# timer.net
KiCad netlist of a schematic drawn in Altium Designer
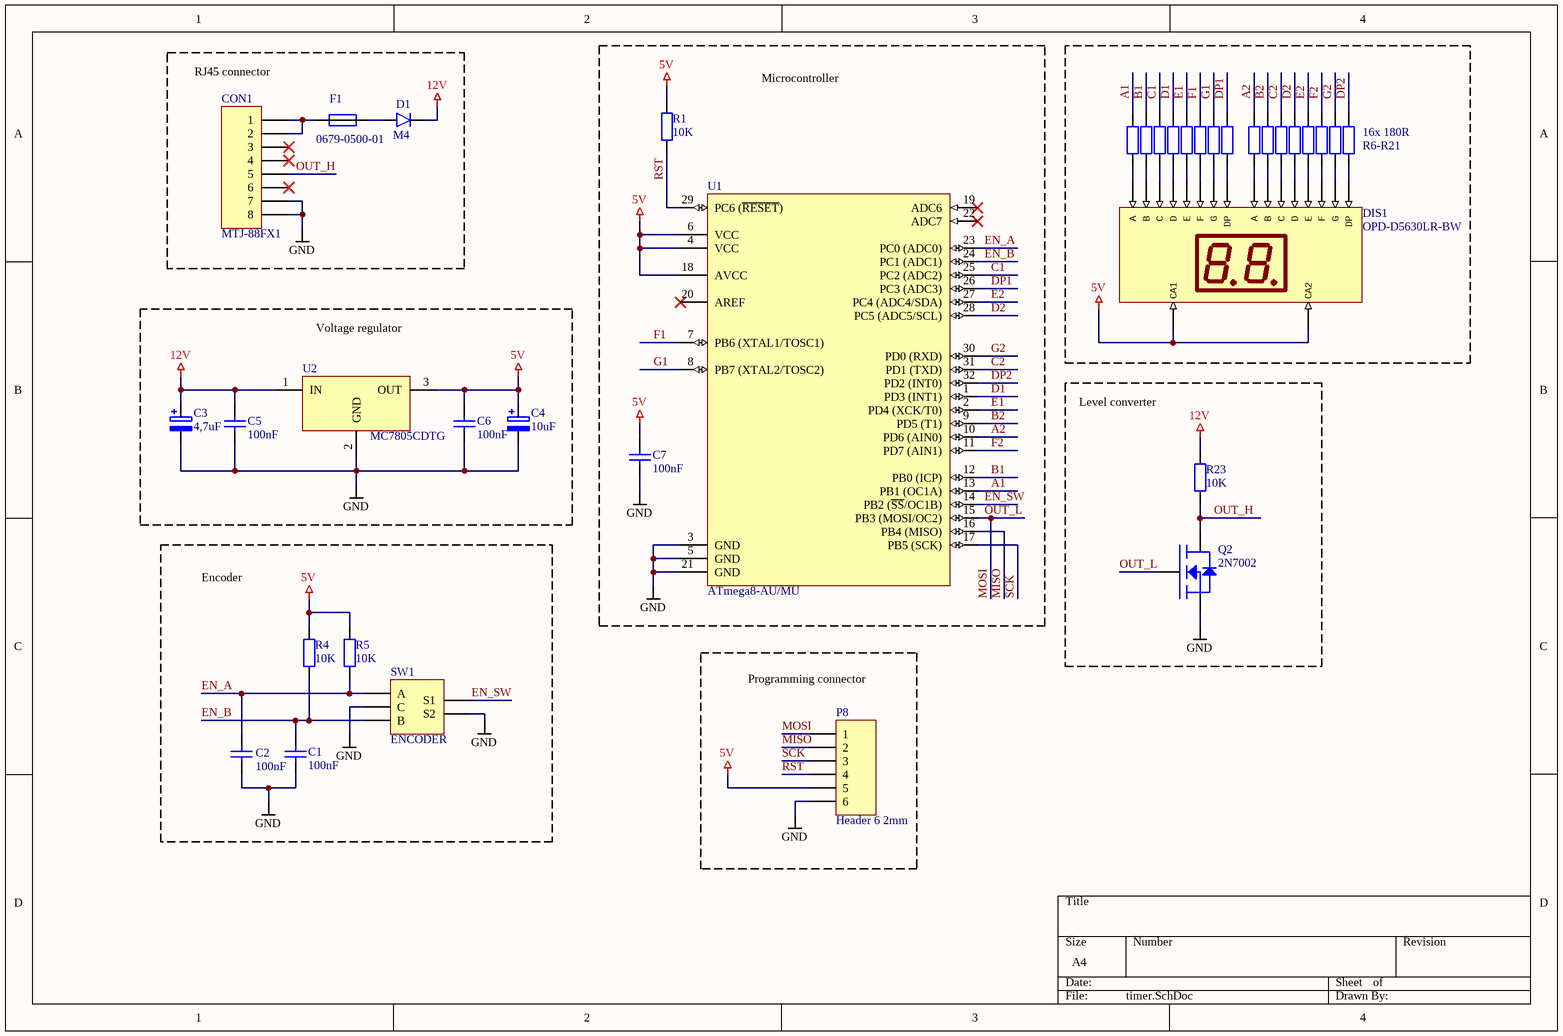
[diagram p0: timer.SchDoc]

(export (version "E")
  (design (tool "Eeschema 10.0.6"))
  (components
    (comp (ref "C1")
      (value "100nF")
      (footprint "C0805")
      (description "Capacitor")
      (libsource (lib "Library") (part "Cap"))
    )
    (comp (ref "C2")
      (value "100nF")
      (footprint "C0805")
      (description "Capacitor")
      (libsource (lib "Library") (part "Cap"))
    )
    (comp (ref "C3")
      (value "4,7uF")
      (footprint "TANC_B")
      (description "Capacitor Polarized")
      (libsource (lib "Library") (part "Cap_Pol"))
    )
    (comp (ref "C4")
      (value "10uF")
      (footprint "TANC_B")
      (description "Capacitor Polarized")
      (libsource (lib "Library") (part "Cap_Pol"))
    )
    (comp (ref "C5")
      (value "100nF")
      (footprint "C0805")
      (description "Capacitor")
      (libsource (lib "Library") (part "Cap"))
    )
    (comp (ref "C6")
      (value "100nF")
      (footprint "C0805")
      (description "Capacitor")
      (libsource (lib "Library") (part "Cap"))
    )
    (comp (ref "C7")
      (value "100nF")
      (footprint "C0805")
      (description "Capacitor")
      (libsource (lib "Library") (part "Cap"))
    )
    (comp (ref "CON1")
      (value "MTJ-88FX1")
      (footprint "MTJ-88FX1")
      (libsource (lib "Connectors") (part "MTJ-88FX1"))
    )
    (comp (ref "D1") (value "M4") (footprint "SMA") (libsource (lib "Library") (part "Diode")))
    (comp (ref "DIS1")
      (value "OPD-D5630LR-BW")
      (footprint "OPD-D5631LR-BW")
      (libsource (lib "Library") (part "2x8SEGMENTS"))
    )
    (comp (ref "F1")
      (value "0679-0500-01")
      (footprint "0679-0500-01")
      (description "Bezpiecznik: topikowy; szybki; ceramiczny; 500mA; 125VAC; 125VDC")
      (libsource (lib "Library") (part "0679-0500-01"))
    )
    (comp (ref "P8")
      (value "Header 6 2mm")
      (footprint "MA06-1_2mm")
      (description "Header, 6-Pin")
      (libsource (lib "Connectors") (part "Header 6"))
    )
    (comp (ref "Q2")
      (value "2N7002")
      (footprint "SOT23")
      (description "N-MOSFET")
      (libsource (lib "Library") (part "2N7002(GSD)"))
    )
    (comp (ref "R1")
      (value "10K")
      (footprint "R0805")
      (description "Resistor")
      (libsource (lib "") (part "Res_1"))
    )
    (comp (ref "R4")
      (value "10K")
      (footprint "R0805")
      (description "Resistor")
      (libsource (lib "Library") (part "Res"))
    )
    (comp (ref "R5")
      (value "10K")
      (footprint "R0805")
      (description "Resistor")
      (libsource (lib "Library") (part "Res"))
    )
    (comp (ref "R6")
      (value "180R")
      (footprint "R0805")
      (description "Resistor")
      (libsource (lib "Library") (part "Res"))
    )
    (comp (ref "R7")
      (value "180R")
      (footprint "R0805")
      (description "Resistor")
      (libsource (lib "Library") (part "Res"))
    )
    (comp (ref "R8")
      (value "180R")
      (footprint "R0805")
      (description "Resistor")
      (libsource (lib "Library") (part "Res"))
    )
    (comp (ref "R9")
      (value "180R")
      (footprint "R0805")
      (description "Resistor")
      (libsource (lib "Library") (part "Res"))
    )
    (comp (ref "R10")
      (value "180R")
      (footprint "R0805")
      (description "Resistor")
      (libsource (lib "Library") (part "Res"))
    )
    (comp (ref "R11")
      (value "180R")
      (footprint "R0805")
      (description "Resistor")
      (libsource (lib "Library") (part "Res"))
    )
    (comp (ref "R12")
      (value "180R")
      (footprint "R0805")
      (description "Resistor")
      (libsource (lib "Library") (part "Res"))
    )
    (comp (ref "R13")
      (value "180R")
      (footprint "R0805")
      (description "Resistor")
      (libsource (lib "Library") (part "Res"))
    )
    (comp (ref "R14")
      (value "180R")
      (footprint "R0805")
      (description "Resistor")
      (libsource (lib "Library") (part "Res"))
    )
    (comp (ref "R15")
      (value "180R")
      (footprint "R0805")
      (description "Resistor")
      (libsource (lib "Library") (part "Res"))
    )
    (comp (ref "R16")
      (value "180R")
      (footprint "R0805")
      (description "Resistor")
      (libsource (lib "Library") (part "Res"))
    )
    (comp (ref "R17")
      (value "180R")
      (footprint "R0805")
      (description "Resistor")
      (libsource (lib "Library") (part "Res"))
    )
    (comp (ref "R18")
      (value "180R")
      (footprint "R0805")
      (description "Resistor")
      (libsource (lib "Library") (part "Res"))
    )
    (comp (ref "R19")
      (value "180R")
      (footprint "R0805")
      (description "Resistor")
      (libsource (lib "Library") (part "Res"))
    )
    (comp (ref "R20")
      (value "180R")
      (footprint "R0805")
      (description "Resistor")
      (libsource (lib "Library") (part "Res"))
    )
    (comp (ref "R21")
      (value "180R")
      (footprint "R0805")
      (description "Resistor")
      (libsource (lib "Library") (part "Res"))
    )
    (comp (ref "R23")
      (value "10K")
      (footprint "R0805")
      (description "Resistor")
      (libsource (lib "Library") (part "Res"))
    )
    (comp (ref "SW1")
      (value "ENCODER")
      (footprint "EC12E20-24P24C-SW")
      (description "EC12E20-24P24C-SW")
      (libsource (lib "Library") (part "ENCODER"))
    )
    (comp (ref "U1")
      (value "ATmega8-AU/MU")
      (footprint "TQFP-32A")
      (description "TQFP - 32pin / MLF - 32pin")
      (libsource (lib "IC") (part "ATmega8-AU/MU"))
    )
    (comp (ref "U2") (value "MC7805CDTG") (footprint "TO-252") (libsource (lib "IC") (part "78xx")))
  )
  (nets
    (net (code "1") (name "/A1") (class "Default")
      (node (ref "R6") (pin "2") (pinfunction "2_2") (pintype "passive"))
      (node (ref "U1") (pin "13") (pinfunction "PB1_(OC1A)_13") (pintype "bidirectional"))
    )
    (net (code "2") (name "/A2") (class "Default")
      (node (ref "R14") (pin "2") (pinfunction "2_2") (pintype "passive"))
      (node (ref "U1") (pin "10") (pinfunction "PD6_(AIN0)_10") (pintype "bidirectional"))
    )
    (net (code "3") (name "/B1") (class "Default")
      (node (ref "R7") (pin "2") (pinfunction "2_2") (pintype "passive"))
      (node (ref "U1") (pin "12") (pinfunction "PB0_(ICP)_12") (pintype "bidirectional"))
    )
    (net (code "4") (name "/B2") (class "Default")
      (node (ref "R15") (pin "2") (pinfunction "2_2") (pintype "passive"))
      (node (ref "U1") (pin "9") (pinfunction "PD5_(T1)_9") (pintype "bidirectional"))
    )
    (net (code "5") (name "/C1") (class "Default")
      (node (ref "R8") (pin "2") (pinfunction "2_2") (pintype "passive"))
      (node (ref "U1") (pin "25") (pinfunction "PC2_(ADC2)_25") (pintype "bidirectional"))
    )
    (net (code "6") (name "/C2") (class "Default")
      (node (ref "R16") (pin "2") (pinfunction "2_2") (pintype "passive"))
      (node (ref "U1") (pin "31") (pinfunction "PD1_(TXD)_31") (pintype "bidirectional"))
    )
    (net (code "7") (name "/D1") (class "Default")
      (node (ref "R9") (pin "2") (pinfunction "2_2") (pintype "passive"))
      (node (ref "U1") (pin "1") (pinfunction "PD3_(INT1)_1") (pintype "bidirectional"))
    )
    (net (code "8") (name "/D2") (class "Default")
      (node (ref "R17") (pin "2") (pinfunction "2_2") (pintype "passive"))
      (node (ref "U1") (pin "28") (pinfunction "PC5_(ADC5/SCL)_28") (pintype "bidirectional"))
    )
    (net (code "9") (name "/DP1") (class "Default")
      (node (ref "R13") (pin "2") (pinfunction "2_2") (pintype "passive"))
      (node (ref "U1") (pin "26") (pinfunction "PC3_(ADC3)_26") (pintype "bidirectional"))
    )
    (net (code "10") (name "/DP2") (class "Default")
      (node (ref "R21") (pin "2") (pinfunction "2_2") (pintype "passive"))
      (node (ref "U1") (pin "32") (pinfunction "PD2_(INT0)_32") (pintype "bidirectional"))
    )
    (net (code "11") (name "/E1") (class "Default")
      (node (ref "R10") (pin "2") (pinfunction "2_2") (pintype "passive"))
      (node (ref "U1") (pin "2") (pinfunction "PD4_(XCK/T0)_2") (pintype "bidirectional"))
    )
    (net (code "12") (name "/E2") (class "Default")
      (node (ref "R18") (pin "2") (pinfunction "2_2") (pintype "passive"))
      (node (ref "U1") (pin "27") (pinfunction "PC4_(ADC4/SDA)_27") (pintype "bidirectional"))
    )
    (net (code "13") (name "/EN_A") (class "Default")
      (node (ref "C2") (pin "1") (pinfunction "1_1") (pintype "passive"))
      (node (ref "R5") (pin "1") (pinfunction "1_1") (pintype "passive"))
      (node (ref "SW1") (pin "A") (pinfunction "A_A") (pintype "passive"))
      (node (ref "U1") (pin "23") (pinfunction "PC0_(ADC0)_23") (pintype "bidirectional"))
    )
    (net (code "14") (name "/EN_B") (class "Default")
      (node (ref "C1") (pin "1") (pinfunction "1_1") (pintype "passive"))
      (node (ref "R4") (pin "1") (pinfunction "1_1") (pintype "passive"))
      (node (ref "SW1") (pin "B") (pinfunction "B_B") (pintype "passive"))
      (node (ref "U1") (pin "24") (pinfunction "PC1_(ADC1)_24") (pintype "bidirectional"))
    )
    (net (code "15") (name "/EN_SW") (class "Default")
      (node (ref "SW1") (pin "S1") (pinfunction "S1_S1") (pintype "passive"))
      (node (ref "U1") (pin "14") (pinfunction "PB2_(~{SS}/OC1B)_14") (pintype "bidirectional"))
    )
    (net (code "16") (name "/F1") (class "Default")
      (node (ref "R11") (pin "2") (pinfunction "2_2") (pintype "passive"))
      (node (ref "U1") (pin "7") (pinfunction "PB6_(XTAL1/TOSC1)_7") (pintype "bidirectional"))
    )
    (net (code "17") (name "/F2") (class "Default")
      (node (ref "R19") (pin "2") (pinfunction "2_2") (pintype "passive"))
      (node (ref "U1") (pin "11") (pinfunction "PD7_(AIN1)_11") (pintype "bidirectional"))
    )
    (net (code "18") (name "/G1") (class "Default")
      (node (ref "R12") (pin "2") (pinfunction "2_2") (pintype "passive"))
      (node (ref "U1") (pin "8") (pinfunction "PB7_(XTAL2/TOSC2)_8") (pintype "bidirectional"))
    )
    (net (code "19") (name "/G2") (class "Default")
      (node (ref "R20") (pin "2") (pinfunction "2_2") (pintype "passive"))
      (node (ref "U1") (pin "30") (pinfunction "PD0_(RXD)_30") (pintype "bidirectional"))
    )
    (net (code "20") (name "/MISO") (class "Default")
      (node (ref "P8") (pin "2") (pinfunction "2_2") (pintype "passive"))
      (node (ref "U1") (pin "16") (pinfunction "PB4_(MISO)_16") (pintype "bidirectional"))
    )
    (net (code "21") (name "/MOSI") (class "Default")
      (node (ref "P8") (pin "1") (pinfunction "1_1") (pintype "passive"))
      (node (ref "Q2") (pin "1") (pinfunction "G_1") (pintype "passive"))
      (node (ref "U1") (pin "15") (pinfunction "PB3_(MOSI/OC2)_15") (pintype "bidirectional"))
    )
    (net (code "22") (name "/OUT_H") (class "Default")
      (node (ref "CON1") (pin "5") (pinfunction "5_5") (pintype "passive"))
      (node (ref "Q2") (pin "3") (pinfunction "D_3") (pintype "passive"))
      (node (ref "R23") (pin "1") (pinfunction "1_1") (pintype "passive"))
    )
    (net (code "23") (name "/RST") (class "Default")
      (node (ref "P8") (pin "4") (pinfunction "4_4") (pintype "passive"))
      (node (ref "R1") (pin "2") (pinfunction "2_2") (pintype "passive"))
      (node (ref "U1") (pin "29") (pinfunction "PC6_(~{RESET})_29") (pintype "bidirectional"))
    )
    (net (code "24") (name "/SCK") (class "Default")
      (node (ref "P8") (pin "3") (pinfunction "3_3") (pintype "passive"))
      (node (ref "U1") (pin "17") (pinfunction "PB5_(SCK)_17") (pintype "bidirectional"))
    )
    (net (code "25") (name "5V") (class "Default")
      (node (ref "C4") (pin "1") (pinfunction "1_1") (pintype "passive"))
      (node (ref "C6") (pin "1") (pinfunction "1_1") (pintype "passive"))
      (node (ref "C7") (pin "1") (pinfunction "1_1") (pintype "passive"))
      (node (ref "DIS1") (pin "13") (pinfunction "CA2_13") (pintype "input"))
      (node (ref "DIS1") (pin "14") (pinfunction "CA1_14") (pintype "input"))
      (node (ref "P8") (pin "5") (pinfunction "5_5") (pintype "passive"))
      (node (ref "R1") (pin "1") (pinfunction "1_1") (pintype "passive"))
      (node (ref "R4") (pin "2") (pinfunction "2_2") (pintype "passive"))
      (node (ref "R5") (pin "2") (pinfunction "2_2") (pintype "passive"))
      (node (ref "U1") (pin "18") (pinfunction "AVCC_18") (pintype "power_in"))
      (node (ref "U1") (pin "4") (pinfunction "VCC_4") (pintype "power_in"))
      (node (ref "U1") (pin "6") (pinfunction "VCC_6") (pintype "power_in"))
      (node (ref "U2") (pin "3") (pinfunction "OUT_3") (pintype "power_in"))
    )
    (net (code "26") (name "12V") (class "Default")
      (node (ref "C3") (pin "1") (pinfunction "1_1") (pintype "passive"))
      (node (ref "C5") (pin "1") (pinfunction "1_1") (pintype "passive"))
      (node (ref "D1") (pin "1") (pinfunction "1_1") (pintype "power_in"))
      (node (ref "R23") (pin "2") (pinfunction "2_2") (pintype "passive"))
      (node (ref "U2") (pin "1") (pinfunction "IN_1") (pintype "power_in"))
    )
    (net (code "27") (name "GND") (class "Default")
      (node (ref "C1") (pin "2") (pinfunction "2_2") (pintype "passive"))
      (node (ref "C2") (pin "2") (pinfunction "2_2") (pintype "passive"))
      (node (ref "C3") (pin "2") (pinfunction "2_2") (pintype "passive"))
      (node (ref "C4") (pin "2") (pinfunction "2_2") (pintype "passive"))
      (node (ref "C5") (pin "2") (pinfunction "2_2") (pintype "passive"))
      (node (ref "C6") (pin "2") (pinfunction "2_2") (pintype "passive"))
      (node (ref "C7") (pin "2") (pinfunction "2_2") (pintype "passive"))
      (node (ref "CON1") (pin "7") (pinfunction "7_7") (pintype "passive"))
      (node (ref "CON1") (pin "8") (pinfunction "8_8") (pintype "passive"))
      (node (ref "P8") (pin "6") (pinfunction "6_6") (pintype "passive"))
      (node (ref "Q2") (pin "2") (pinfunction "S_2") (pintype "passive"))
      (node (ref "SW1") (pin "C") (pinfunction "C_C") (pintype "passive"))
      (node (ref "SW1") (pin "S2") (pinfunction "S2_S2") (pintype "passive"))
      (node (ref "U1") (pin "21") (pinfunction "GND_21") (pintype "power_in"))
      (node (ref "U1") (pin "3") (pinfunction "GND_3") (pintype "power_in"))
      (node (ref "U1") (pin "5") (pinfunction "GND_5") (pintype "power_in"))
      (node (ref "U2") (pin "2") (pinfunction "GND_2") (pintype "power_in"))
    )
    (net (code "28") (name "Net-(CON1-Pad1)") (class "Default")
      (node (ref "CON1") (pin "1") (pinfunction "1_1") (pintype "passive"))
      (node (ref "CON1") (pin "2") (pinfunction "2_2") (pintype "passive"))
      (node (ref "F1") (pin "1") (pinfunction "1_1") (pintype "passive"))
    )
    (net (code "29") (name "Net-(D1-Pad2)") (class "Default")
      (node (ref "D1") (pin "2") (pinfunction "2_2") (pintype "power_in"))
      (node (ref "F1") (pin "2") (pinfunction "2_2") (pintype "passive"))
    )
    (net (code "30") (name "Net-(DIS1-A-Pad11)") (class "Default")
      (node (ref "DIS1") (pin "11") (pinfunction "A_11") (pintype "input"))
      (node (ref "R14") (pin "1") (pinfunction "1_1") (pintype "passive"))
    )
    (net (code "31") (name "Net-(DIS1-A-Pad16)") (class "Default")
      (node (ref "DIS1") (pin "16") (pinfunction "A_16") (pintype "input"))
      (node (ref "R6") (pin "1") (pinfunction "1_1") (pintype "passive"))
    )
    (net (code "32") (name "Net-(DIS1-B-Pad10)") (class "Default")
      (node (ref "DIS1") (pin "10") (pinfunction "B_10") (pintype "input"))
      (node (ref "R15") (pin "1") (pinfunction "1_1") (pintype "passive"))
    )
    (net (code "33") (name "Net-(DIS1-B-Pad15)") (class "Default")
      (node (ref "DIS1") (pin "15") (pinfunction "B_15") (pintype "input"))
      (node (ref "R7") (pin "1") (pinfunction "1_1") (pintype "passive"))
    )
    (net (code "34") (name "Net-(DIS1-C-Pad3)") (class "Default")
      (node (ref "DIS1") (pin "3") (pinfunction "C_3") (pintype "input"))
      (node (ref "R8") (pin "1") (pinfunction "1_1") (pintype "passive"))
    )
    (net (code "35") (name "Net-(DIS1-C-Pad8)") (class "Default")
      (node (ref "DIS1") (pin "8") (pinfunction "C_8") (pintype "input"))
      (node (ref "R16") (pin "1") (pinfunction "1_1") (pintype "passive"))
    )
    (net (code "36") (name "Net-(DIS1-D-Pad2)") (class "Default")
      (node (ref "DIS1") (pin "2") (pinfunction "D_2") (pintype "input"))
      (node (ref "R9") (pin "1") (pinfunction "1_1") (pintype "passive"))
    )
    (net (code "37") (name "Net-(DIS1-D-Pad6)") (class "Default")
      (node (ref "DIS1") (pin "6") (pinfunction "D_6") (pintype "input"))
      (node (ref "R17") (pin "1") (pinfunction "1_1") (pintype "passive"))
    )
    (net (code "38") (name "Net-(DIS1-DP-Pad4)") (class "Default")
      (node (ref "DIS1") (pin "4") (pinfunction "DP_4") (pintype "input"))
      (node (ref "R13") (pin "1") (pinfunction "1_1") (pintype "passive"))
    )
    (net (code "39") (name "Net-(DIS1-DP-Pad9)") (class "Default")
      (node (ref "DIS1") (pin "9") (pinfunction "DP_9") (pintype "input"))
      (node (ref "R21") (pin "1") (pinfunction "1_1") (pintype "passive"))
    )
    (net (code "40") (name "Net-(DIS1-E-Pad1)") (class "Default")
      (node (ref "DIS1") (pin "1") (pinfunction "E_1") (pintype "input"))
      (node (ref "R10") (pin "1") (pinfunction "1_1") (pintype "passive"))
    )
    (net (code "41") (name "Net-(DIS1-E-Pad5)") (class "Default")
      (node (ref "DIS1") (pin "5") (pinfunction "E_5") (pintype "input"))
      (node (ref "R18") (pin "1") (pinfunction "1_1") (pintype "passive"))
    )
    (net (code "42") (name "Net-(DIS1-F-Pad12)") (class "Default")
      (node (ref "DIS1") (pin "12") (pinfunction "F_12") (pintype "input"))
      (node (ref "R19") (pin "1") (pinfunction "1_1") (pintype "passive"))
    )
    (net (code "43") (name "Net-(DIS1-F-Pad18)") (class "Default")
      (node (ref "DIS1") (pin "18") (pinfunction "F_18") (pintype "input"))
      (node (ref "R11") (pin "1") (pinfunction "1_1") (pintype "passive"))
    )
    (net (code "44") (name "Net-(DIS1-G-Pad7)") (class "Default")
      (node (ref "DIS1") (pin "7") (pinfunction "G_7") (pintype "input"))
      (node (ref "R20") (pin "1") (pinfunction "1_1") (pintype "passive"))
    )
    (net (code "45") (name "Net-(DIS1-G-Pad17)") (class "Default")
      (node (ref "DIS1") (pin "17") (pinfunction "G_17") (pintype "input"))
      (node (ref "R12") (pin "1") (pinfunction "1_1") (pintype "passive"))
    )
    (net (code "46") (name "unconnected-(CON1-Pad3)") (class "Default")
      (node (ref "CON1") (pin "3") (pinfunction "3_3") (pintype "passive+no_connect"))
    )
    (net (code "47") (name "unconnected-(CON1-Pad4)") (class "Default")
      (node (ref "CON1") (pin "4") (pinfunction "4_4") (pintype "passive+no_connect"))
    )
    (net (code "48") (name "unconnected-(CON1-Pad6)") (class "Default")
      (node (ref "CON1") (pin "6") (pinfunction "6_6") (pintype "passive+no_connect"))
    )
    (net (code "49") (name "unconnected-(U1-ADC6-Pad19)") (class "Default")
      (node (ref "U1") (pin "19") (pinfunction "ADC6_19") (pintype "input+no_connect"))
    )
    (net (code "50") (name "unconnected-(U1-ADC7-Pad22)") (class "Default")
      (node (ref "U1") (pin "22") (pinfunction "ADC7_22") (pintype "input+no_connect"))
    )
    (net (code "51") (name "unconnected-(U1-AREF-Pad20)") (class "Default")
      (node (ref "U1") (pin "20") (pinfunction "AREF_20") (pintype "passive+no_connect"))
    )
  )
)
